# ownduino-metaboard-alt2.net
KiCad netlist of a schematic drawn in EAGLE
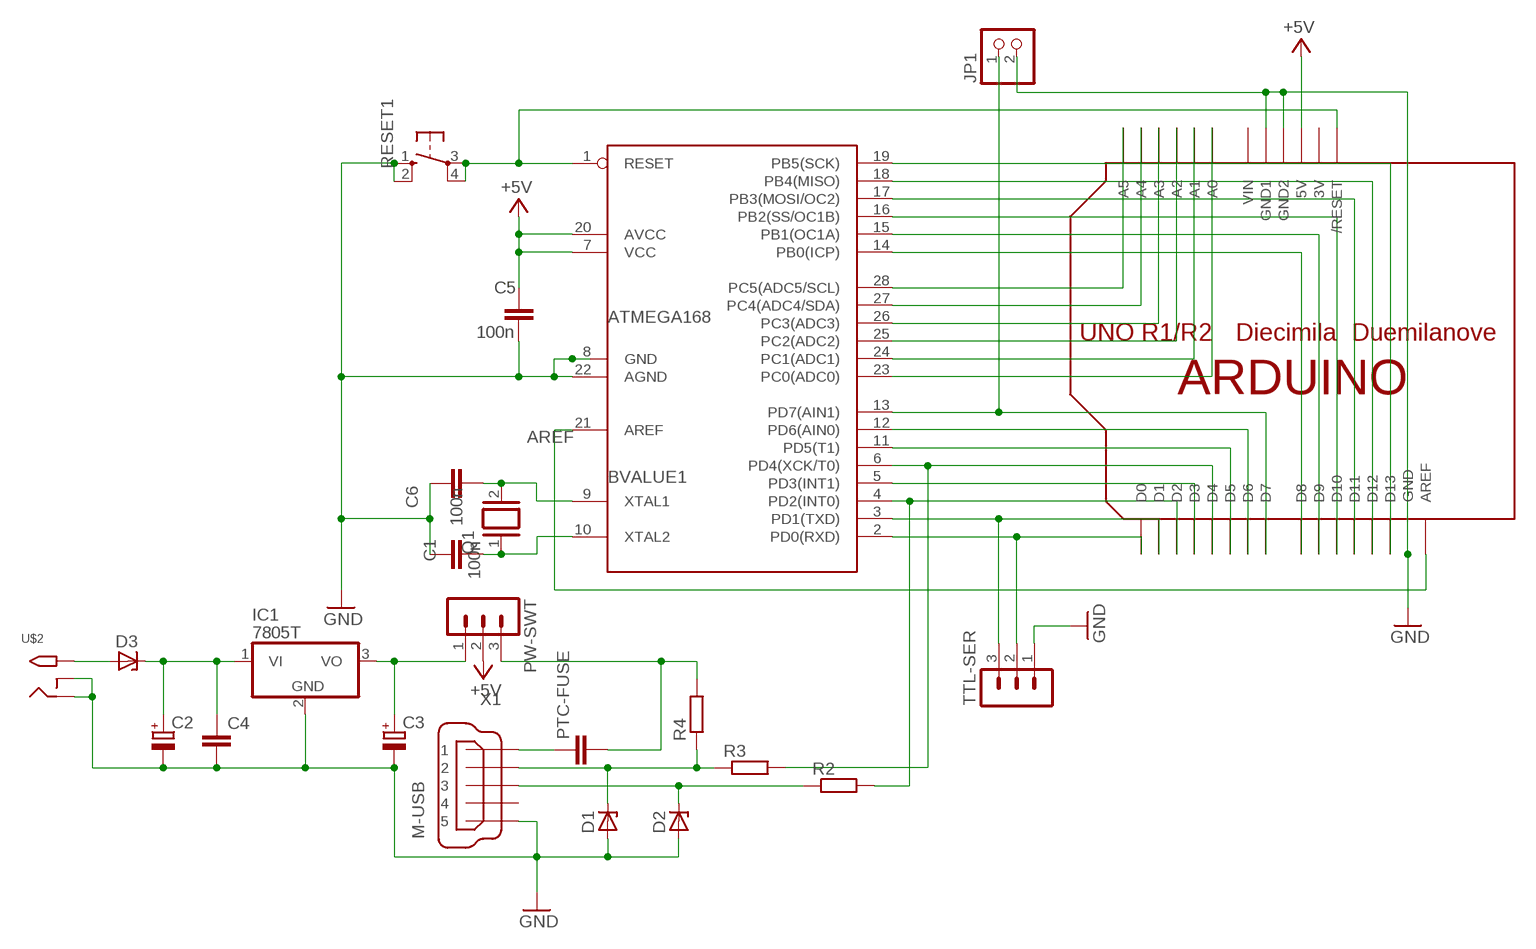
[diagram p0: schematic, sheet 1]

(export (version "E")
  (design (tool "Eeschema 10.0.6"))
  (components
    (comp (ref "BVALUE1")
      (value "ATMEGA168")
      (footprint "eagle-import:DIL28-3")
      (libsource (lib "eagle-import") (part "MEGA8-P"))
    )
    (comp (ref "C1")
      (value "100n")
      (footprint "eagle-import:C025-024X044")
      (libsource (lib "eagle-import") (part "C-EU025-024X044"))
    )
    (comp (ref "C2")
      (value "CPOL-EUE2.5-6")
      (footprint "eagle-import:E2,5-6")
      (libsource (lib "eagle-import") (part "CPOL-EUE2.5-6"))
    )
    (comp (ref "C3")
      (value "CPOL-EUE2.5-6")
      (footprint "eagle-import:E2,5-6")
      (libsource (lib "eagle-import") (part "CPOL-EUE2.5-6"))
    )
    (comp (ref "C4")
      (value "C-EU025-025X050")
      (footprint "eagle-import:C025-025X050")
      (libsource (lib "eagle-import") (part "C-EU025-025X050"))
    )
    (comp (ref "C5")
      (value "100n")
      (footprint "eagle-import:C025-024X044")
      (libsource (lib "eagle-import") (part "C-EU025-024X044"))
    )
    (comp (ref "C6")
      (value "100n")
      (footprint "eagle-import:C025-024X044")
      (libsource (lib "eagle-import") (part "C-EU025-024X044"))
    )
    (comp (ref "D1")
      (value "ZENER-DIODEZD-7.5")
      (footprint "eagle-import:ZDIO-7.5")
      (libsource (lib "eagle-import") (part "ZENER-DIODEZD-7.5"))
    )
    (comp (ref "D2")
      (value "ZENER-DIODEZD-5")
      (footprint "eagle-import:ZDIO-5")
      (libsource (lib "eagle-import") (part "ZENER-DIODEZD-5"))
    )
    (comp (ref "D3")
      (value "ZENER-DIODEZD-7.5")
      (footprint "eagle-import:ZDIO-7.5")
      (libsource (lib "eagle-import") (part "ZENER-DIODEZD-7.5"))
    )
    (comp (ref "IC1")
      (value "7805T")
      (footprint "eagle-import:TO220H")
      (libsource (lib "eagle-import") (part "78T05"))
    )
    (comp (ref "JP1")
      (value "PINHD-1X2")
      (footprint "eagle-import:1X02")
      (libsource (lib "eagle-import") (part "PINHD-1X2"))
    )
    (comp (ref "PTC-FUSE")
      (value "C-EU025_050-025X075")
      (footprint "eagle-import:C025_050-025X075")
      (libsource (lib "eagle-import") (part "C-EU025_050-025X075"))
    )
    (comp (ref "PW-SWT")
      (value "MA03-1")
      (footprint "eagle-import:MA03-1")
      (libsource (lib "eagle-import") (part "MA03-1"))
    )
    (comp (ref "Q1")
      (value "XTAL/S")
      (footprint "eagle-import:QS")
      (libsource (lib "eagle-import") (part "XTAL/S"))
    )
    (comp (ref "R2")
      (value "R-EU_0207/12")
      (footprint "eagle-import:0207_12")
      (libsource (lib "eagle-import") (part "R-EU_0207/12"))
    )
    (comp (ref "R3")
      (value "R-EU_0207/10")
      (footprint "eagle-import:0207_10")
      (libsource (lib "eagle-import") (part "R-EU_0207/10"))
    )
    (comp (ref "R4")
      (value "R-EU_0207/10")
      (footprint "eagle-import:0207_10")
      (libsource (lib "eagle-import") (part "R-EU_0207/10"))
    )
    (comp (ref "RESET1")
      (value "10-XX")
      (footprint "eagle-import:B3F-10XX")
      (libsource (lib "eagle-import") (part "10-XX"))
    )
    (comp (ref "TTL-SER")
      (value "MA03-1")
      (footprint "eagle-import:MA03-1")
      (fields (field (name "OC_FARNELL") "unknown") (field (name "OC_NEWARK") "unknown"))
      (libsource (lib "eagle-import") (part "MA03-1"))
    )
    (comp (ref "U$1")
      (value "ARDUINOUNO")
      (footprint "eagle-import:ARDUINO")
      (libsource (lib "eagle-import") (part "ARDUINOUNO"))
    )
    (comp (ref "U$2")
      (value "2.1MMJACKTHM")
      (footprint "eagle-import:PJ-102A")
      (libsource (lib "eagle-import") (part "2.1MMJACKTHM"))
    )
    (comp (ref "X1")
      (value "M-USB")
      (footprint "eagle-import:32005-601")
      (libsource (lib "eagle-import") (part "MINI-USB_SHIELD5P2-32005-601"))
    )
  )
  (nets
    (net (code "1") (name "+5V") (class "Default")
      (node (ref "BVALUE1") (pin "20") (pinfunction "AVCC_20") (pintype "bidirectional"))
      (node (ref "BVALUE1") (pin "7") (pinfunction "VCC_7") (pintype "bidirectional"))
      (node (ref "C5") (pin "1") (pinfunction "1_1") (pintype "passive"))
      (node (ref "PW-SWT") (pin "2") (pinfunction "2_2") (pintype "passive"))
      (node (ref "U$1") (pin "5V") (pinfunction "5V_5V") (pintype "power_in"))
    )
    (net (code "2") (name "/3V") (class "Default")
      (node (ref "U$1") (pin "3V") (pinfunction "3V_3V") (pintype "power_in"))
    )
    (net (code "3") (name "/AREF") (class "Default")
      (node (ref "BVALUE1") (pin "21") (pinfunction "AREF_21") (pintype "bidirectional"))
      (node (ref "U$1") (pin "AREF") (pinfunction "AREF_AREF") (pintype "bidirectional"))
    )
    (net (code "4") (name "/VIN") (class "Default")
      (node (ref "U$1") (pin "VIN") (pinfunction "VIN_VIN") (pintype "power_in"))
    )
    (net (code "5") (name "GND") (class "Default")
      (node (ref "BVALUE1") (pin "22") (pinfunction "AGND_22") (pintype "bidirectional"))
      (node (ref "BVALUE1") (pin "8") (pinfunction "GND_8") (pintype "bidirectional"))
      (node (ref "C1") (pin "1") (pinfunction "1_1") (pintype "passive"))
      (node (ref "C2") (pin "-") (pinfunction "-_-") (pintype "passive"))
      (node (ref "C3") (pin "-") (pinfunction "-_-") (pintype "passive"))
      (node (ref "C4") (pin "2") (pinfunction "2_2") (pintype "passive"))
      (node (ref "C5") (pin "2") (pinfunction "2_2") (pintype "passive"))
      (node (ref "C6") (pin "1") (pinfunction "1_1") (pintype "passive"))
      (node (ref "D1") (pin "A") (pinfunction "A_A") (pintype "passive"))
      (node (ref "D2") (pin "A") (pinfunction "A_A") (pintype "passive"))
      (node (ref "IC1") (pin "2") (pinfunction "GND_2") (pintype "passive"))
      (node (ref "JP1") (pin "2") (pinfunction "2_2") (pintype "passive"))
      (node (ref "RESET1") (pin "1") (pinfunction "S_1") (pintype "passive"))
      (node (ref "RESET1") (pin "2") (pinfunction "S1_2") (pintype "passive"))
      (node (ref "TTL-SER") (pin "1") (pinfunction "1_1") (pintype "passive"))
      (node (ref "U$1") (pin "GND") (pinfunction "GND_GND") (pintype "power_in"))
      (node (ref "U$1") (pin "GND1") (pinfunction "GND1_GND1") (pintype "power_in"))
      (node (ref "U$1") (pin "GND2") (pinfunction "GND2_GND2") (pintype "power_in"))
      (node (ref "U$2") (pin "RING") (pinfunction "RING_RING") (pintype "bidirectional"))
      (node (ref "U$2") (pin "RING_SW") (pinfunction "RING_SW_RING_SW") (pintype "bidirectional"))
      (node (ref "X1") (pin "5") (pinfunction "5_5") (pintype "passive"))
    )
    (net (code "6") (name "Net-(BVALUE1-PB0(ICP))") (class "Default")
      (node (ref "BVALUE1") (pin "14") (pinfunction "PB0(ICP)_14") (pintype "bidirectional"))
      (node (ref "U$1") (pin "D8") (pinfunction "D8_D8") (pintype "bidirectional"))
    )
    (net (code "7") (name "Net-(BVALUE1-PB1(OC1A))") (class "Default")
      (node (ref "BVALUE1") (pin "15") (pinfunction "PB1(OC1A)_15") (pintype "bidirectional"))
      (node (ref "U$1") (pin "D9") (pinfunction "D9_D9") (pintype "bidirectional"))
    )
    (net (code "8") (name "Net-(BVALUE1-PB2(SS{slash}OC1B))") (class "Default")
      (node (ref "BVALUE1") (pin "16") (pinfunction "PB2(SS/OC1B)_16") (pintype "bidirectional"))
      (node (ref "U$1") (pin "D10") (pinfunction "D10_D10") (pintype "bidirectional"))
    )
    (net (code "9") (name "Net-(BVALUE1-PB3(MOSI{slash}OC2))") (class "Default")
      (node (ref "BVALUE1") (pin "17") (pinfunction "PB3(MOSI/OC2)_17") (pintype "bidirectional"))
      (node (ref "U$1") (pin "D11") (pinfunction "D11_D11") (pintype "bidirectional"))
    )
    (net (code "10") (name "Net-(BVALUE1-PB4(MISO))") (class "Default")
      (node (ref "BVALUE1") (pin "18") (pinfunction "PB4(MISO)_18") (pintype "bidirectional"))
      (node (ref "U$1") (pin "D12") (pinfunction "D12_D12") (pintype "bidirectional"))
    )
    (net (code "11") (name "Net-(BVALUE1-PB5(SCK))") (class "Default")
      (node (ref "BVALUE1") (pin "19") (pinfunction "PB5(SCK)_19") (pintype "bidirectional"))
      (node (ref "U$1") (pin "D13") (pinfunction "D13_D13") (pintype "bidirectional"))
    )
    (net (code "12") (name "Net-(BVALUE1-PC0(ADC0))") (class "Default")
      (node (ref "BVALUE1") (pin "23") (pinfunction "PC0(ADC0)_23") (pintype "bidirectional"))
      (node (ref "U$1") (pin "A0") (pinfunction "A0_A0") (pintype "bidirectional"))
    )
    (net (code "13") (name "Net-(BVALUE1-PC1(ADC1))") (class "Default")
      (node (ref "BVALUE1") (pin "24") (pinfunction "PC1(ADC1)_24") (pintype "bidirectional"))
      (node (ref "U$1") (pin "A1") (pinfunction "A1_A1") (pintype "bidirectional"))
    )
    (net (code "14") (name "Net-(BVALUE1-PC2(ADC2))") (class "Default")
      (node (ref "BVALUE1") (pin "25") (pinfunction "PC2(ADC2)_25") (pintype "bidirectional"))
      (node (ref "U$1") (pin "A2") (pinfunction "A2_A2") (pintype "bidirectional"))
    )
    (net (code "15") (name "Net-(BVALUE1-PC3(ADC3))") (class "Default")
      (node (ref "BVALUE1") (pin "26") (pinfunction "PC3(ADC3)_26") (pintype "bidirectional"))
      (node (ref "U$1") (pin "A3") (pinfunction "A3_A3") (pintype "bidirectional"))
    )
    (net (code "16") (name "Net-(BVALUE1-PC4(ADC4{slash}SDA))") (class "Default")
      (node (ref "BVALUE1") (pin "27") (pinfunction "PC4(ADC4/SDA)_27") (pintype "bidirectional"))
      (node (ref "U$1") (pin "A4") (pinfunction "A4_A4") (pintype "bidirectional"))
    )
    (net (code "17") (name "Net-(BVALUE1-PC5(ADC5{slash}SCL))") (class "Default")
      (node (ref "BVALUE1") (pin "28") (pinfunction "PC5(ADC5/SCL)_28") (pintype "bidirectional"))
      (node (ref "U$1") (pin "A5") (pinfunction "A5_A5") (pintype "bidirectional"))
    )
    (net (code "18") (name "Net-(BVALUE1-PD0(RXD))") (class "Default")
      (node (ref "BVALUE1") (pin "2") (pinfunction "PD0(RXD)_2") (pintype "bidirectional"))
      (node (ref "TTL-SER") (pin "2") (pinfunction "2_2") (pintype "passive"))
      (node (ref "U$1") (pin "D0") (pinfunction "D0_D0") (pintype "bidirectional"))
    )
    (net (code "19") (name "Net-(BVALUE1-PD1(TXD))") (class "Default")
      (node (ref "BVALUE1") (pin "3") (pinfunction "PD1(TXD)_3") (pintype "bidirectional"))
      (node (ref "TTL-SER") (pin "3") (pinfunction "3_3") (pintype "passive"))
      (node (ref "U$1") (pin "D1") (pinfunction "D1_D1") (pintype "bidirectional"))
    )
    (net (code "20") (name "Net-(BVALUE1-PD2(INT0))") (class "Default")
      (node (ref "BVALUE1") (pin "4") (pinfunction "PD2(INT0)_4") (pintype "bidirectional"))
      (node (ref "R2") (pin "2") (pinfunction "2_2") (pintype "passive"))
      (node (ref "U$1") (pin "D2") (pinfunction "D2_D2") (pintype "bidirectional"))
    )
    (net (code "21") (name "Net-(BVALUE1-PD3(INT1))") (class "Default")
      (node (ref "BVALUE1") (pin "5") (pinfunction "PD3(INT1)_5") (pintype "bidirectional"))
      (node (ref "U$1") (pin "D3") (pinfunction "D3_D3") (pintype "bidirectional"))
    )
    (net (code "22") (name "Net-(BVALUE1-PD4(XCK{slash}T0))") (class "Default")
      (node (ref "BVALUE1") (pin "6") (pinfunction "PD4(XCK/T0)_6") (pintype "bidirectional"))
      (node (ref "R3") (pin "2") (pinfunction "2_2") (pintype "passive"))
      (node (ref "U$1") (pin "D4") (pinfunction "D4_D4") (pintype "bidirectional"))
    )
    (net (code "23") (name "Net-(BVALUE1-PD5(T1))") (class "Default")
      (node (ref "BVALUE1") (pin "11") (pinfunction "PD5(T1)_11") (pintype "bidirectional"))
      (node (ref "U$1") (pin "D5") (pinfunction "D5_D5") (pintype "bidirectional"))
    )
    (net (code "24") (name "Net-(BVALUE1-PD6(AIN0))") (class "Default")
      (node (ref "BVALUE1") (pin "12") (pinfunction "PD6(AIN0)_12") (pintype "bidirectional"))
      (node (ref "U$1") (pin "D6") (pinfunction "D6_D6") (pintype "bidirectional"))
    )
    (net (code "25") (name "Net-(BVALUE1-PD7(AIN1))") (class "Default")
      (node (ref "BVALUE1") (pin "13") (pinfunction "PD7(AIN1)_13") (pintype "bidirectional"))
      (node (ref "JP1") (pin "1") (pinfunction "1_1") (pintype "passive"))
      (node (ref "U$1") (pin "D7") (pinfunction "D7_D7") (pintype "bidirectional"))
    )
    (net (code "26") (name "Net-(BVALUE1-RESET)") (class "Default")
      (node (ref "BVALUE1") (pin "1") (pinfunction "RESET_1") (pintype "bidirectional"))
      (node (ref "RESET1") (pin "3") (pinfunction "P_3") (pintype "passive"))
      (node (ref "RESET1") (pin "4") (pinfunction "P1_4") (pintype "passive"))
      (node (ref "U$1") (pin "RESET") (pinfunction "/RESET_RESET") (pintype "bidirectional"))
    )
    (net (code "27") (name "Net-(BVALUE1-XTAL1)") (class "Default")
      (node (ref "BVALUE1") (pin "9") (pinfunction "XTAL1_9") (pintype "bidirectional"))
      (node (ref "C6") (pin "2") (pinfunction "2_2") (pintype "passive"))
      (node (ref "Q1") (pin "2") (pinfunction "2_2") (pintype "passive"))
    )
    (net (code "28") (name "Net-(BVALUE1-XTAL2)") (class "Default")
      (node (ref "BVALUE1") (pin "10") (pinfunction "XTAL2_10") (pintype "bidirectional"))
      (node (ref "C1") (pin "2") (pinfunction "2_2") (pintype "passive"))
      (node (ref "Q1") (pin "1") (pinfunction "1_1") (pintype "passive"))
    )
    (net (code "29") (name "Net-(D1-PadC)") (class "Default")
      (node (ref "D1") (pin "C") (pinfunction "C_C") (pintype "passive"))
      (node (ref "R3") (pin "1") (pinfunction "1_1") (pintype "passive"))
      (node (ref "R4") (pin "1") (pinfunction "1_1") (pintype "passive"))
      (node (ref "X1") (pin "2") (pinfunction "2_2") (pintype "passive"))
    )
    (net (code "30") (name "Net-(D2-PadC)") (class "Default")
      (node (ref "D2") (pin "C") (pinfunction "C_C") (pintype "passive"))
      (node (ref "R2") (pin "1") (pinfunction "1_1") (pintype "passive"))
      (node (ref "X1") (pin "3") (pinfunction "3_3") (pintype "passive"))
    )
    (net (code "31") (name "Net-(D3-PadA)") (class "Default")
      (node (ref "D3") (pin "A") (pinfunction "A_A") (pintype "passive"))
      (node (ref "U$2") (pin "TIP") (pinfunction "TIP_TIP") (pintype "bidirectional"))
    )
    (net (code "32") (name "Net-(IC1-VI)") (class "Default")
      (node (ref "C2") (pin "+") (pinfunction "+_+") (pintype "passive"))
      (node (ref "C4") (pin "1") (pinfunction "1_1") (pintype "passive"))
      (node (ref "D3") (pin "C") (pinfunction "C_C") (pintype "passive"))
      (node (ref "IC1") (pin "1") (pinfunction "VI_1") (pintype "input"))
    )
    (net (code "33") (name "Net-(IC1-VO)") (class "Default")
      (node (ref "C3") (pin "+") (pinfunction "+_+") (pintype "passive"))
      (node (ref "IC1") (pin "3") (pinfunction "VO_3") (pintype "passive"))
      (node (ref "PW-SWT") (pin "1") (pinfunction "1_1") (pintype "passive"))
    )
    (net (code "34") (name "Net-(PTC-FUSE-Pad1)") (class "Default")
      (node (ref "PTC-FUSE") (pin "1") (pinfunction "1_1") (pintype "passive"))
      (node (ref "X1") (pin "1") (pinfunction "1_1") (pintype "passive"))
    )
    (net (code "35") (name "Net-(PTC-FUSE-Pad2)") (class "Default")
      (node (ref "PTC-FUSE") (pin "2") (pinfunction "2_2") (pintype "passive"))
      (node (ref "PW-SWT") (pin "3") (pinfunction "3_3") (pintype "passive"))
      (node (ref "R4") (pin "2") (pinfunction "2_2") (pintype "passive"))
    )
    (net (code "36") (name "unconnected-(X1-Pad4)") (class "Default")
      (node (ref "X1") (pin "4") (pinfunction "4_4") (pintype "passive"))
    )
  )
)
